# simple_eq_5532.net
KiCad netlist of a schematic drawn in EAGLE
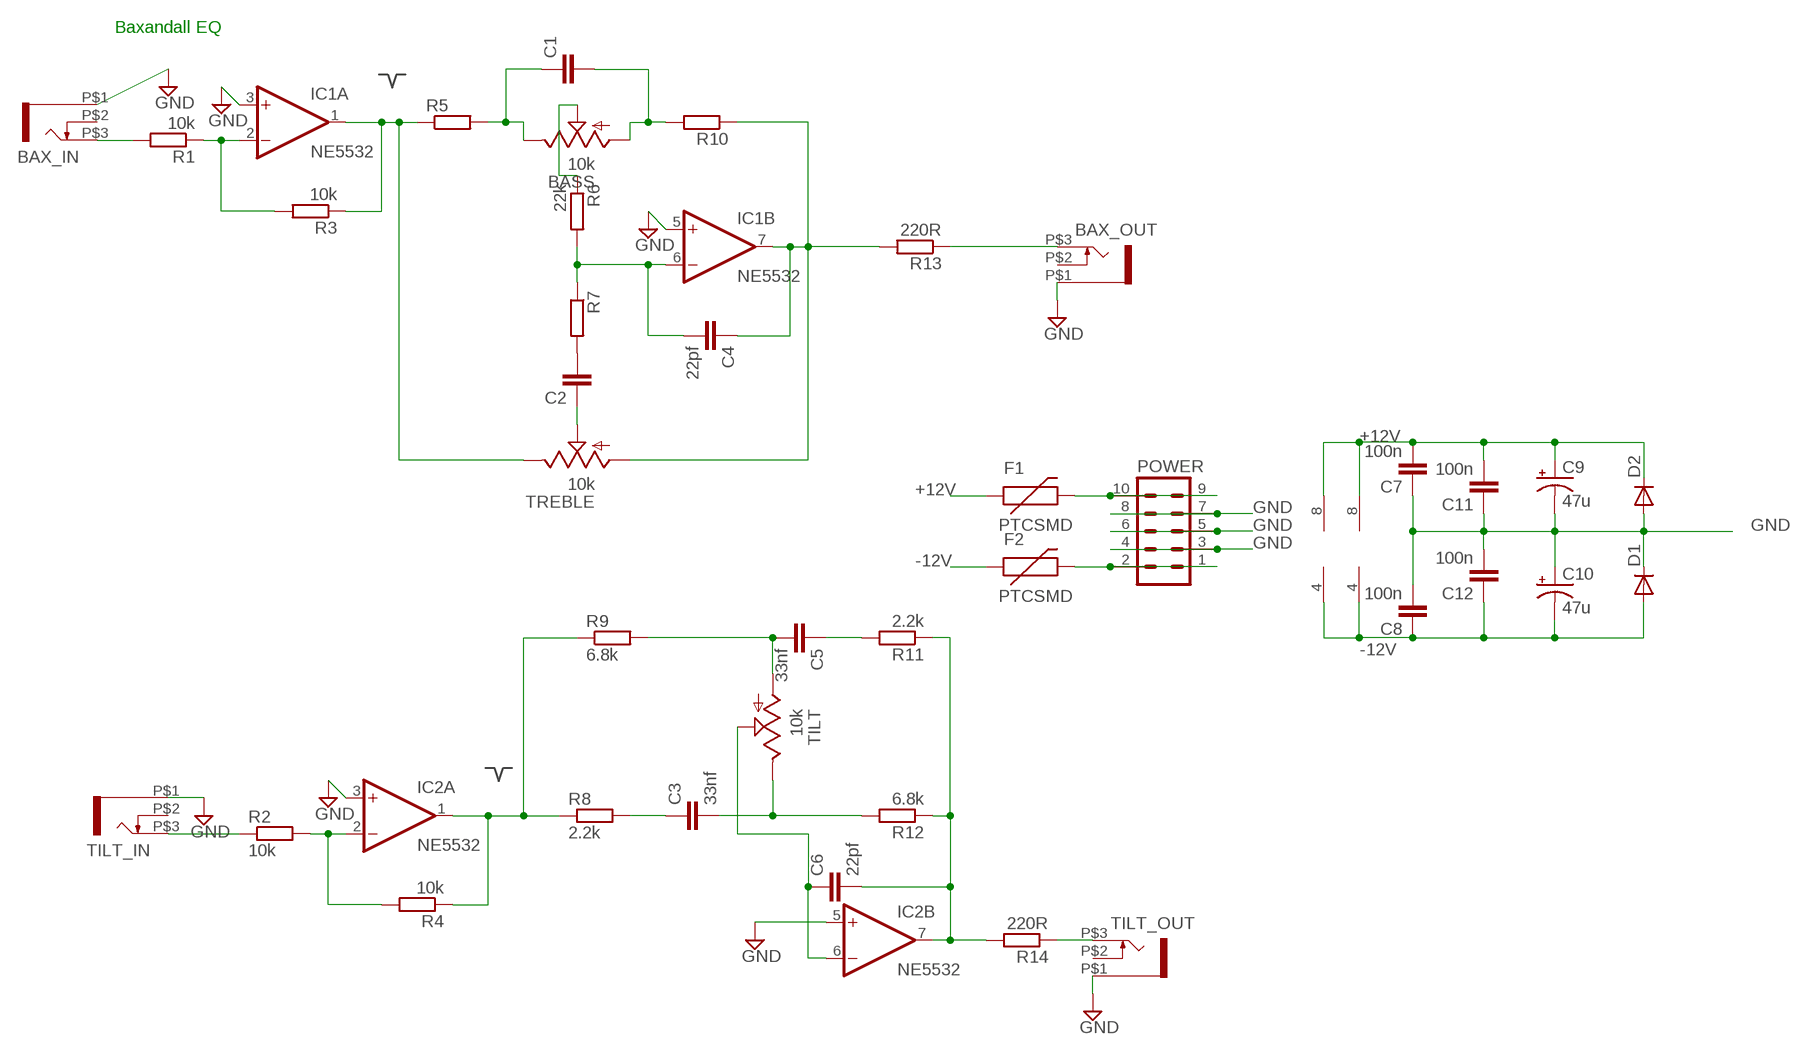
[diagram p0: schematic, sheet 1]

(export (version "E")
  (design (tool "Eeschema 10.0.6"))
  (components
    (comp (ref "BASS")
      (value "10k")
      (footprint "eagle-import:EVUF")
      (libsource (lib "eagle-import") (part "ALPHA-9MMAF2"))
    )
    (comp (ref "BAX_IN")
      (value "THONKICONN")
      (footprint "eagle-import:THONKICONN")
      (libsource (lib "eagle-import") (part "THONKICONN"))
    )
    (comp (ref "BAX_OUT")
      (value "THONKICONN")
      (footprint "eagle-import:THONKICONN")
      (libsource (lib "eagle-import") (part "THONKICONN"))
    )
    (comp (ref "C1")
      (value "C-EU0805_CAP")
      (footprint "eagle-import:R0805")
      (libsource (lib "eagle-import") (part "C-EU0805_CAP"))
    )
    (comp (ref "C2")
      (value "C-EU0805_CAP")
      (footprint "eagle-import:R0805")
      (libsource (lib "eagle-import") (part "C-EU0805_CAP"))
    )
    (comp (ref "C3")
      (value "33nf")
      (footprint "eagle-import:R0805")
      (libsource (lib "eagle-import") (part "C-EU0805_CAP"))
    )
    (comp (ref "C4")
      (value "22pf")
      (footprint "eagle-import:R0805")
      (libsource (lib "eagle-import") (part "C-EU0805_CAP"))
    )
    (comp (ref "C5")
      (value "33nf")
      (footprint "eagle-import:R0805")
      (libsource (lib "eagle-import") (part "C-EU0805_CAP"))
    )
    (comp (ref "C6")
      (value "22pf")
      (footprint "eagle-import:R0805")
      (libsource (lib "eagle-import") (part "C-EU0805_CAP"))
    )
    (comp (ref "C7")
      (value "100n")
      (footprint "eagle-import:R0805")
      (libsource (lib "eagle-import") (part "C-EU0805_CAP"))
    )
    (comp (ref "C8")
      (value "100n")
      (footprint "eagle-import:R0805")
      (libsource (lib "eagle-import") (part "C-EU0805_CAP"))
    )
    (comp (ref "C9")
      (value "47u")
      (footprint "eagle-import:PANASONIC_D")
      (libsource (lib "eagle-import") (part "CPOL-USD"))
    )
    (comp (ref "C10")
      (value "47u")
      (footprint "eagle-import:PANASONIC_D")
      (libsource (lib "eagle-import") (part "CPOL-USD"))
    )
    (comp (ref "C11")
      (value "100n")
      (footprint "eagle-import:R0805")
      (libsource (lib "eagle-import") (part "C-EU0805_CAP"))
    )
    (comp (ref "C12")
      (value "100n")
      (footprint "eagle-import:R0805")
      (libsource (lib "eagle-import") (part "C-EU0805_CAP"))
    )
    (comp (ref "D1")
      (value "DIODE-SOD123")
      (footprint "eagle-import:SOD123")
      (libsource (lib "eagle-import") (part "DIODE-SOD123"))
    )
    (comp (ref "D2")
      (value "DIODE-SOD123")
      (footprint "eagle-import:SOD123")
      (libsource (lib "eagle-import") (part "DIODE-SOD123"))
    )
    (comp (ref "F1")
      (value "PTCSMD")
      (footprint "eagle-import:PTC-1206")
      (libsource (lib "eagle-import") (part "PTCSMD"))
    )
    (comp (ref "F2")
      (value "PTCSMD")
      (footprint "eagle-import:PTC-1206")
      (libsource (lib "eagle-import") (part "PTCSMD"))
    )
    (comp (ref "IC1")
      (value "NE5532")
      (footprint "eagle-import:SO08")
      (libsource (lib "eagle-import") (part "TL072D"))
    )
    (comp (ref "IC2")
      (value "NE5532")
      (footprint "eagle-import:SO08")
      (libsource (lib "eagle-import") (part "TL072D"))
    )
    (comp (ref "POWER")
      (value "10_PIN_HEADER")
      (footprint "eagle-import:MA05-2")
      (libsource (lib "eagle-import") (part "10_PIN_HEADER"))
    )
    (comp (ref "R1")
      (value "10k")
      (footprint "eagle-import:R0805")
      (libsource (lib "eagle-import") (part "R-EU_R0805"))
    )
    (comp (ref "R2")
      (value "10k")
      (footprint "eagle-import:R0805")
      (libsource (lib "eagle-import") (part "R-EU_R0805"))
    )
    (comp (ref "R3")
      (value "10k")
      (footprint "eagle-import:R0805")
      (libsource (lib "eagle-import") (part "R-EU_R0805"))
    )
    (comp (ref "R4")
      (value "10k")
      (footprint "eagle-import:R0805")
      (libsource (lib "eagle-import") (part "R-EU_R0805"))
    )
    (comp (ref "R5")
      (value "R-EU_R0805")
      (footprint "eagle-import:R0805")
      (libsource (lib "eagle-import") (part "R-EU_R0805"))
    )
    (comp (ref "R6")
      (value "22k")
      (footprint "eagle-import:R0805")
      (libsource (lib "eagle-import") (part "R-EU_R0805"))
    )
    (comp (ref "R7")
      (value "R-EU_R0805")
      (footprint "eagle-import:R0805")
      (libsource (lib "eagle-import") (part "R-EU_R0805"))
    )
    (comp (ref "R8")
      (value "2.2k")
      (footprint "eagle-import:R0805")
      (libsource (lib "eagle-import") (part "R-EU_R0805"))
    )
    (comp (ref "R9")
      (value "6.8k")
      (footprint "eagle-import:R0805")
      (libsource (lib "eagle-import") (part "R-EU_R0805"))
    )
    (comp (ref "R10")
      (value "R-EU_R0805")
      (footprint "eagle-import:R0805")
      (libsource (lib "eagle-import") (part "R-EU_R0805"))
    )
    (comp (ref "R11")
      (value "2.2k")
      (footprint "eagle-import:R0805")
      (libsource (lib "eagle-import") (part "R-EU_R0805"))
    )
    (comp (ref "R12")
      (value "6.8k")
      (footprint "eagle-import:R0805")
      (libsource (lib "eagle-import") (part "R-EU_R0805"))
    )
    (comp (ref "R13")
      (value "220R")
      (footprint "eagle-import:R0805")
      (libsource (lib "eagle-import") (part "R-EU_R0805"))
    )
    (comp (ref "R14")
      (value "220R")
      (footprint "eagle-import:R0805")
      (libsource (lib "eagle-import") (part "R-EU_R0805"))
    )
    (comp (ref "TILT")
      (value "10k")
      (footprint "eagle-import:EVUF")
      (libsource (lib "eagle-import") (part "ALPHA-9MMAF2"))
    )
    (comp (ref "TILT_IN")
      (value "THONKICONN")
      (footprint "eagle-import:THONKICONN")
      (libsource (lib "eagle-import") (part "THONKICONN"))
    )
    (comp (ref "TILT_OUT")
      (value "THONKICONN")
      (footprint "eagle-import:THONKICONN")
      (libsource (lib "eagle-import") (part "THONKICONN"))
    )
    (comp (ref "TREBLE")
      (value "10k")
      (footprint "eagle-import:EVUF")
      (libsource (lib "eagle-import") (part "ALPHA-9MMAF2"))
    )
  )
  (nets
    (net (code "1") (name "/+12V") (class "Default")
      (node (ref "C11") (pin "2") (pinfunction "2_2") (pintype "passive"))
      (node (ref "C7") (pin "2") (pinfunction "2_2") (pintype "passive"))
      (node (ref "C9") (pin "+") (pinfunction "+_+") (pintype "passive"))
      (node (ref "D2") (pin "C") (pinfunction "C_C") (pintype "passive"))
      (node (ref "F1") (pin "1") (pinfunction "1_1") (pintype "bidirectional"))
      (node (ref "IC1") (pin "8") (pinfunction "V+_8") (pintype "power_in"))
      (node (ref "IC2") (pin "8") (pinfunction "V+_8") (pintype "power_in"))
    )
    (net (code "2") (name "/-12V") (class "Default")
      (node (ref "C10") (pin "-") (pinfunction "-_-") (pintype "passive"))
      (node (ref "C12") (pin "1") (pinfunction "1_1") (pintype "passive"))
      (node (ref "C8") (pin "1") (pinfunction "1_1") (pintype "passive"))
      (node (ref "D1") (pin "A") (pinfunction "A_A") (pintype "passive"))
      (node (ref "F2") (pin "1") (pinfunction "1_1") (pintype "bidirectional"))
      (node (ref "IC1") (pin "4") (pinfunction "V-_4") (pintype "power_in"))
      (node (ref "IC2") (pin "4") (pinfunction "V-_4") (pintype "power_in"))
    )
    (net (code "3") (name "GND") (class "Default")
      (node (ref "BAX_IN") (pin "P$1") (pinfunction "5_P$1") (pintype "passive"))
      (node (ref "BAX_OUT") (pin "P$1") (pinfunction "5_P$1") (pintype "passive"))
      (node (ref "C10") (pin "+") (pinfunction "+_+") (pintype "passive"))
      (node (ref "C11") (pin "1") (pinfunction "1_1") (pintype "passive"))
      (node (ref "C12") (pin "2") (pinfunction "2_2") (pintype "passive"))
      (node (ref "C7") (pin "1") (pinfunction "1_1") (pintype "passive"))
      (node (ref "C8") (pin "2") (pinfunction "2_2") (pintype "passive"))
      (node (ref "C9") (pin "-") (pinfunction "-_-") (pintype "passive"))
      (node (ref "D1") (pin "C") (pinfunction "C_C") (pintype "passive"))
      (node (ref "D2") (pin "A") (pinfunction "A_A") (pintype "passive"))
      (node (ref "IC1") (pin "3") (pinfunction "+IN_3") (pintype "input"))
      (node (ref "IC1") (pin "5") (pinfunction "+IN_5") (pintype "input"))
      (node (ref "IC2") (pin "3") (pinfunction "+IN_3") (pintype "input"))
      (node (ref "IC2") (pin "5") (pinfunction "+IN_5") (pintype "input"))
      (node (ref "POWER") (pin "3") (pinfunction "3_3") (pintype "passive"))
      (node (ref "POWER") (pin "4") (pinfunction "4_4") (pintype "passive"))
      (node (ref "POWER") (pin "5") (pinfunction "5_5") (pintype "passive"))
      (node (ref "POWER") (pin "6") (pinfunction "6_6") (pintype "passive"))
      (node (ref "POWER") (pin "7") (pinfunction "7_7") (pintype "passive"))
      (node (ref "POWER") (pin "8") (pinfunction "8_8") (pintype "passive"))
      (node (ref "TILT_IN") (pin "P$1") (pinfunction "5_P$1") (pintype "passive"))
      (node (ref "TILT_OUT") (pin "P$1") (pinfunction "5_P$1") (pintype "passive"))
    )
    (net (code "4") (name "Net-(BASS-A)") (class "Default")
      (node (ref "BASS") (pin "1") (pinfunction "A_1") (pintype "passive"))
      (node (ref "C1") (pin "2") (pinfunction "2_2") (pintype "passive"))
      (node (ref "R10") (pin "2") (pinfunction "2_2") (pintype "passive"))
    )
    (net (code "5") (name "Net-(BASS-E)") (class "Default")
      (node (ref "BASS") (pin "3") (pinfunction "E_3") (pintype "passive"))
      (node (ref "C1") (pin "1") (pinfunction "1_1") (pintype "passive"))
      (node (ref "R5") (pin "2") (pinfunction "2_2") (pintype "passive"))
    )
    (net (code "6") (name "Net-(BASS-S)") (class "Default")
      (node (ref "BASS") (pin "2") (pinfunction "S_2") (pintype "passive"))
      (node (ref "R6") (pin "1") (pinfunction "1_1") (pintype "passive"))
    )
    (net (code "7") (name "Net-(BAX_IN-3)") (class "Default")
      (node (ref "BAX_IN") (pin "P$3") (pinfunction "3_P$3") (pintype "passive"))
      (node (ref "R1") (pin "2") (pinfunction "2_2") (pintype "passive"))
    )
    (net (code "8") (name "Net-(BAX_OUT-3)") (class "Default")
      (node (ref "BAX_OUT") (pin "P$3") (pinfunction "3_P$3") (pintype "passive"))
      (node (ref "R13") (pin "1") (pinfunction "1_1") (pintype "passive"))
    )
    (net (code "9") (name "Net-(C2-Pad2)") (class "Default")
      (node (ref "C2") (pin "2") (pinfunction "2_2") (pintype "passive"))
      (node (ref "R7") (pin "2") (pinfunction "2_2") (pintype "passive"))
    )
    (net (code "10") (name "Net-(C3-Pad1)") (class "Default")
      (node (ref "C3") (pin "1") (pinfunction "1_1") (pintype "passive"))
      (node (ref "R8") (pin "2") (pinfunction "2_2") (pintype "passive"))
    )
    (net (code "11") (name "Net-(C5-Pad1)") (class "Default")
      (node (ref "C5") (pin "1") (pinfunction "1_1") (pintype "passive"))
      (node (ref "R11") (pin "2") (pinfunction "2_2") (pintype "passive"))
    )
    (net (code "12") (name "Net-(F1-Pad2)") (class "Default")
      (node (ref "F1") (pin "2") (pinfunction "2_2") (pintype "bidirectional"))
      (node (ref "POWER") (pin "10") (pinfunction "10_10") (pintype "passive"))
      (node (ref "POWER") (pin "9") (pinfunction "9_9") (pintype "passive"))
    )
    (net (code "13") (name "Net-(F2-Pad2)") (class "Default")
      (node (ref "F2") (pin "2") (pinfunction "2_2") (pintype "bidirectional"))
      (node (ref "POWER") (pin "1") (pinfunction "1_1") (pintype "passive"))
      (node (ref "POWER") (pin "2") (pinfunction "2_2") (pintype "passive"))
    )
    (net (code "14") (name "Net-(IC1A--IN)") (class "Default")
      (node (ref "IC1") (pin "2") (pinfunction "-IN_2") (pintype "input"))
      (node (ref "R1") (pin "1") (pinfunction "1_1") (pintype "passive"))
      (node (ref "R3") (pin "2") (pinfunction "2_2") (pintype "passive"))
    )
    (net (code "15") (name "Net-(IC1A-OUT)") (class "Default")
      (node (ref "IC1") (pin "1") (pinfunction "OUT_1") (pintype "output"))
      (node (ref "R3") (pin "1") (pinfunction "1_1") (pintype "passive"))
      (node (ref "R5") (pin "1") (pinfunction "1_1") (pintype "passive"))
      (node (ref "TREBLE") (pin "3") (pinfunction "E_3") (pintype "passive"))
    )
    (net (code "16") (name "Net-(IC1B--IN)") (class "Default")
      (node (ref "C4") (pin "2") (pinfunction "2_2") (pintype "passive"))
      (node (ref "IC1") (pin "6") (pinfunction "-IN_6") (pintype "input"))
      (node (ref "R6") (pin "2") (pinfunction "2_2") (pintype "passive"))
      (node (ref "R7") (pin "1") (pinfunction "1_1") (pintype "passive"))
    )
    (net (code "17") (name "Net-(IC1B-OUT)") (class "Default")
      (node (ref "C4") (pin "1") (pinfunction "1_1") (pintype "passive"))
      (node (ref "IC1") (pin "7") (pinfunction "OUT_7") (pintype "output"))
      (node (ref "R10") (pin "1") (pinfunction "1_1") (pintype "passive"))
      (node (ref "R13") (pin "2") (pinfunction "2_2") (pintype "passive"))
      (node (ref "TREBLE") (pin "1") (pinfunction "A_1") (pintype "passive"))
    )
    (net (code "18") (name "Net-(IC2A--IN)") (class "Default")
      (node (ref "IC2") (pin "2") (pinfunction "-IN_2") (pintype "input"))
      (node (ref "R2") (pin "2") (pinfunction "2_2") (pintype "passive"))
      (node (ref "R4") (pin "2") (pinfunction "2_2") (pintype "passive"))
    )
    (net (code "19") (name "Net-(IC2A-OUT)") (class "Default")
      (node (ref "IC2") (pin "1") (pinfunction "OUT_1") (pintype "output"))
      (node (ref "R4") (pin "1") (pinfunction "1_1") (pintype "passive"))
      (node (ref "R8") (pin "1") (pinfunction "1_1") (pintype "passive"))
      (node (ref "R9") (pin "1") (pinfunction "1_1") (pintype "passive"))
    )
    (net (code "20") (name "Net-(IC2B--IN)") (class "Default")
      (node (ref "C6") (pin "1") (pinfunction "1_1") (pintype "passive"))
      (node (ref "IC2") (pin "6") (pinfunction "-IN_6") (pintype "input"))
      (node (ref "TILT") (pin "2") (pinfunction "S_2") (pintype "passive"))
    )
    (net (code "21") (name "Net-(IC2B-OUT)") (class "Default")
      (node (ref "C6") (pin "2") (pinfunction "2_2") (pintype "passive"))
      (node (ref "IC2") (pin "7") (pinfunction "OUT_7") (pintype "output"))
      (node (ref "R11") (pin "1") (pinfunction "1_1") (pintype "passive"))
      (node (ref "R12") (pin "1") (pinfunction "1_1") (pintype "passive"))
      (node (ref "R14") (pin "2") (pinfunction "2_2") (pintype "passive"))
    )
    (net (code "22") (name "Net-(TILT-A)") (class "Default")
      (node (ref "C5") (pin "2") (pinfunction "2_2") (pintype "passive"))
      (node (ref "R9") (pin "2") (pinfunction "2_2") (pintype "passive"))
      (node (ref "TILT") (pin "1") (pinfunction "A_1") (pintype "passive"))
    )
    (net (code "23") (name "Net-(TILT-E)") (class "Default")
      (node (ref "C3") (pin "2") (pinfunction "2_2") (pintype "passive"))
      (node (ref "R12") (pin "2") (pinfunction "2_2") (pintype "passive"))
      (node (ref "TILT") (pin "3") (pinfunction "E_3") (pintype "passive"))
    )
    (net (code "24") (name "Net-(TILT_IN-3)") (class "Default")
      (node (ref "R2") (pin "1") (pinfunction "1_1") (pintype "passive"))
      (node (ref "TILT_IN") (pin "P$3") (pinfunction "3_P$3") (pintype "passive"))
    )
    (net (code "25") (name "Net-(TILT_OUT-3)") (class "Default")
      (node (ref "R14") (pin "1") (pinfunction "1_1") (pintype "passive"))
      (node (ref "TILT_OUT") (pin "P$3") (pinfunction "3_P$3") (pintype "passive"))
    )
    (net (code "26") (name "Net-(TREBLE-S)") (class "Default")
      (node (ref "C2") (pin "1") (pinfunction "1_1") (pintype "passive"))
      (node (ref "TREBLE") (pin "2") (pinfunction "S_2") (pintype "passive"))
    )
    (net (code "27") (name "unconnected-(BAX_IN-4-PadP$2)") (class "Default")
      (node (ref "BAX_IN") (pin "P$2") (pinfunction "4_P$2") (pintype "passive"))
    )
    (net (code "28") (name "unconnected-(BAX_OUT-4-PadP$2)") (class "Default")
      (node (ref "BAX_OUT") (pin "P$2") (pinfunction "4_P$2") (pintype "passive"))
    )
    (net (code "29") (name "unconnected-(TILT_IN-4-PadP$2)") (class "Default")
      (node (ref "TILT_IN") (pin "P$2") (pinfunction "4_P$2") (pintype "passive"))
    )
    (net (code "30") (name "unconnected-(TILT_OUT-4-PadP$2)") (class "Default")
      (node (ref "TILT_OUT") (pin "P$2") (pinfunction "4_P$2") (pintype "passive"))
    )
  )
)
